# SurfaceEEG_V1_4.net
KiCad netlist of a schematic drawn in EAGLE
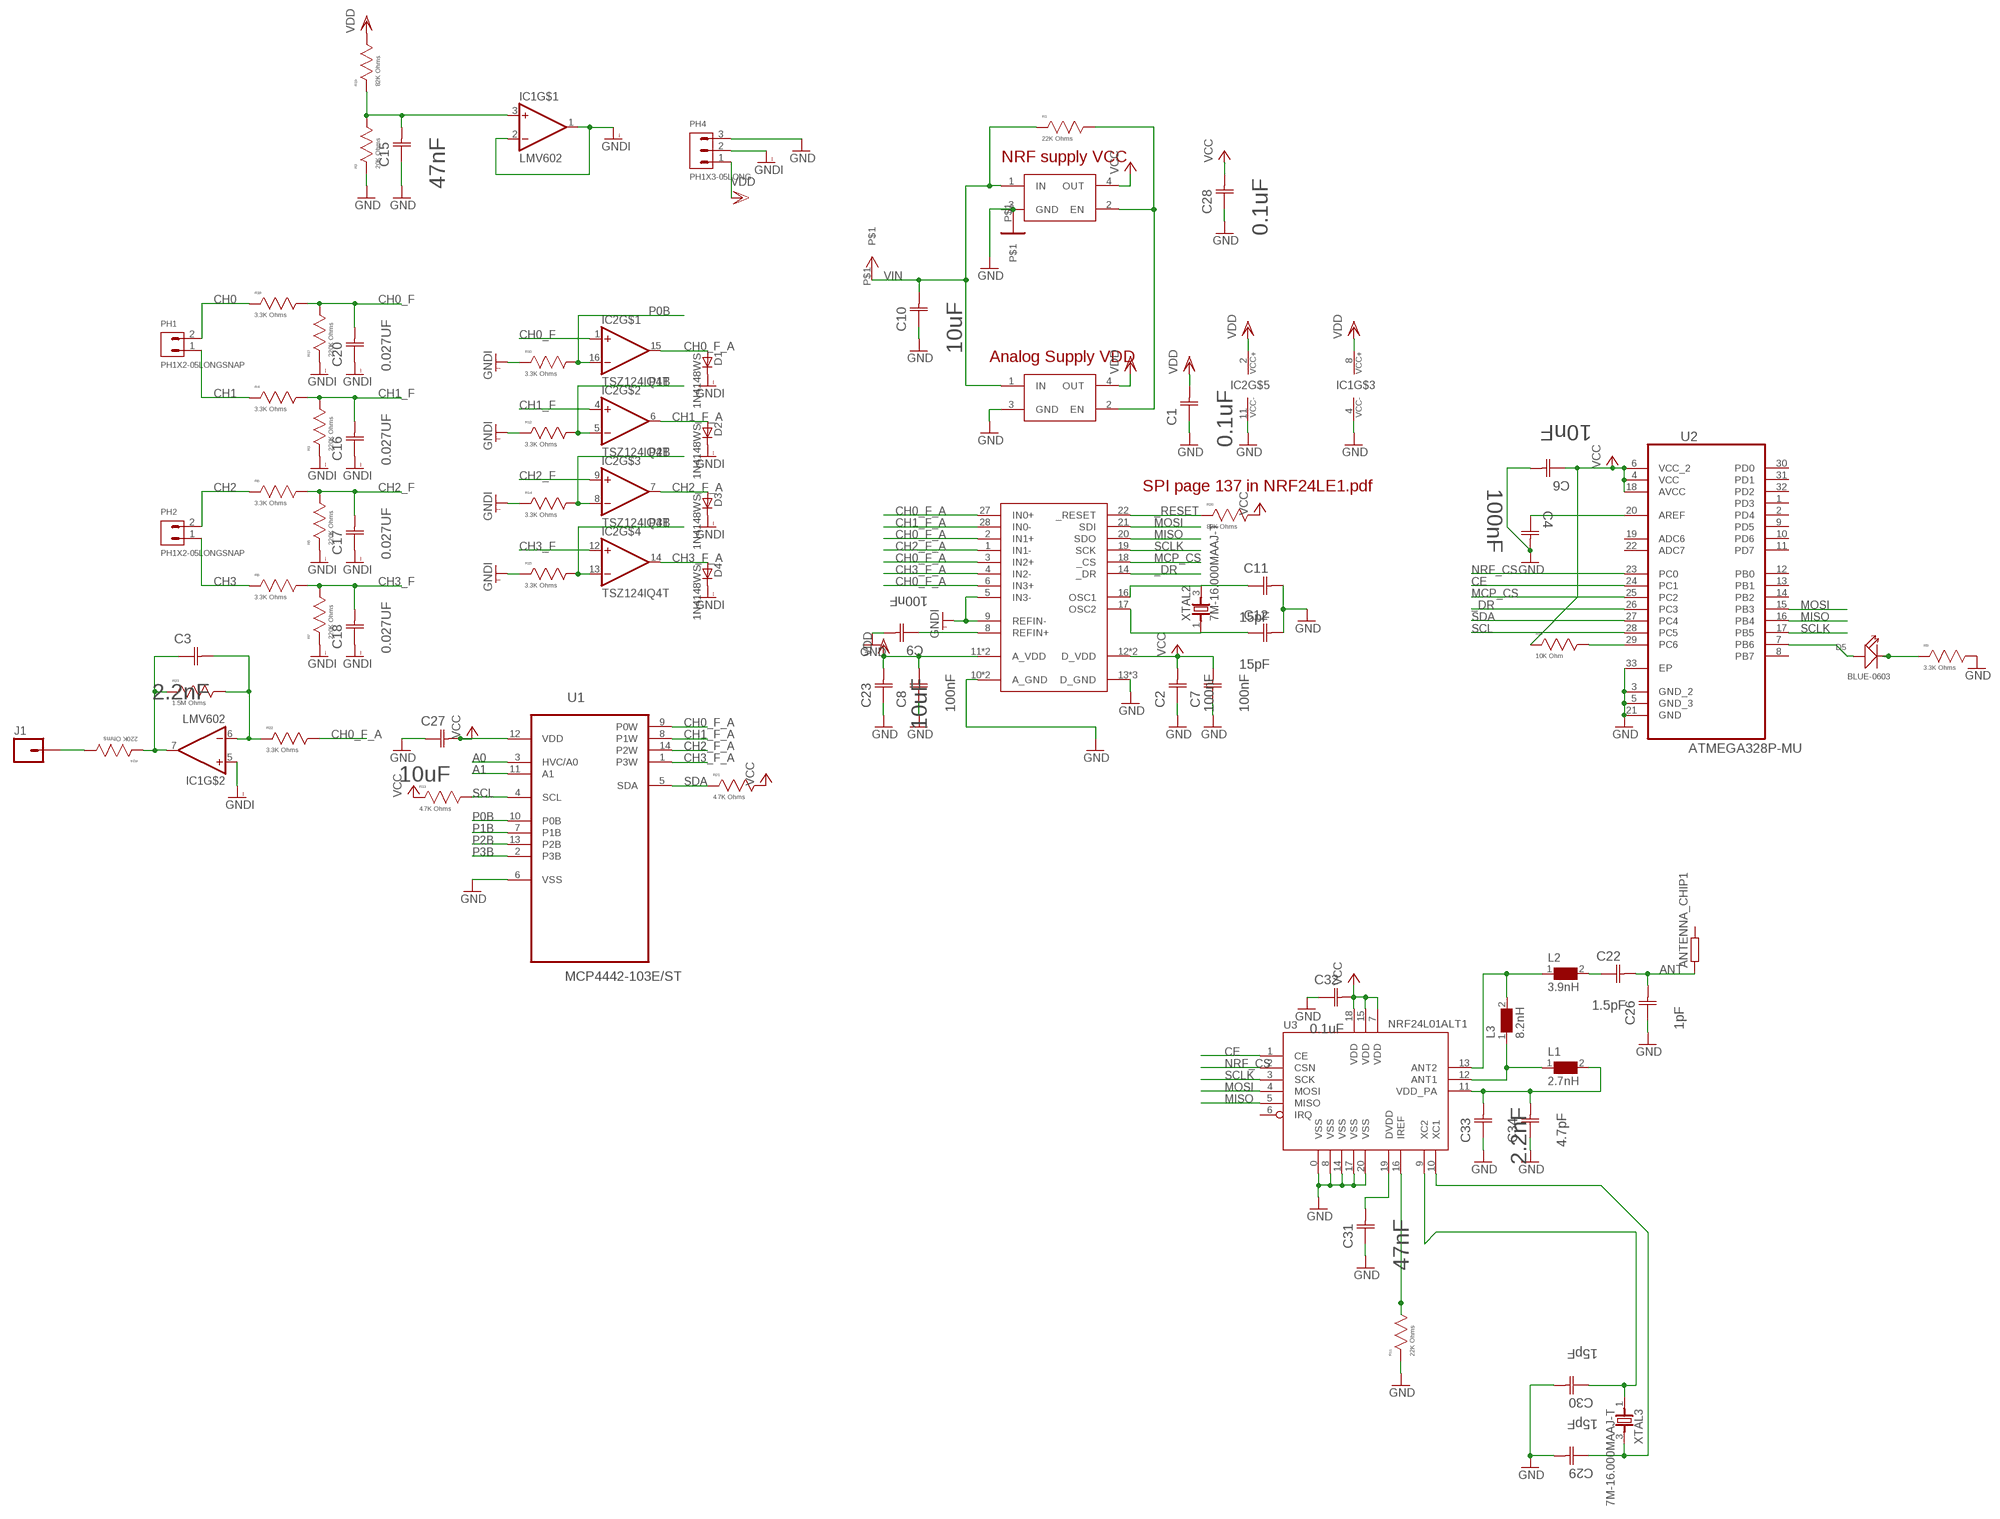
[diagram p0: schematic, sheet 1]

(export (version "E")
  (design (tool "Eeschema 10.0.6"))
  (components
    (comp (ref "ANTENNA_CHIP1")
      (value "R0805")
      (footprint "eagle-import:R0805")
      (libsource (lib "eagle-import") (part "R0805"))
    )
    (comp (ref "C1")
      (value "0.1uF")
      (footprint "eagle-import:CAPC1608X85N")
      (fields (field (name "MPN") "C0603C104K5RAC-TU") (field (name "TOLERANCE") "±10%"))
      (libsource (lib "eagle-import") (part "C0603C104K5RAC-TU"))
    )
    (comp (ref "C2")
      (value "100nF")
      (footprint "eagle-import:CAPC1608X90N")
      (fields (field (name "MPN") "06033C104JAT2A") (field (name "TOLERANCE") "±5%"))
      (libsource (lib "eagle-import") (part "06033C104JAT2A"))
    )
    (comp (ref "C3")
      (value "2.2nF")
      (footprint "eagle-import:CAPC1005X60N")
      (fields (field (name "MPN") "C0402C222K5RACTU") (field (name "TOLERANCE") "±10%"))
      (libsource (lib "eagle-import") (part "C0402C222K5RACTU"))
    )
    (comp (ref "C4")
      (value "100nF")
      (footprint "eagle-import:CAPC1608X85N")
      (fields (field (name "MPN") "C0603C104K4RACTU") (field (name "TOLERANCE") "±10%"))
      (libsource (lib "eagle-import") (part "C0603C104K4RACTU"))
    )
    (comp (ref "C6")
      (value "10nF")
      (footprint "eagle-import:CAPC1608X85N")
      (fields (field (name "MPN") "C0603C103J3GACTU") (field (name "TOLERANCE") "±5%"))
      (libsource (lib "eagle-import") (part "C0603C103J3GACTU"))
    )
    (comp (ref "C7")
      (value "100nF")
      (footprint "eagle-import:CAPC1608X90N")
      (fields (field (name "MPN") "06033C104JAT2A") (field (name "TOLERANCE") "±5%"))
      (libsource (lib "eagle-import") (part "06033C104JAT2A"))
    )
    (comp (ref "C8")
      (value "100nF")
      (footprint "eagle-import:CAPC1608X90N")
      (fields (field (name "MPN") "06033C104JAT2A") (field (name "TOLERANCE") "±5%"))
      (libsource (lib "eagle-import") (part "06033C104JAT2A"))
    )
    (comp (ref "C9")
      (value "100nF")
      (footprint "eagle-import:CAPC1608X90N")
      (fields (field (name "MPN") "06033C104JAT2A") (field (name "TOLERANCE") "±5%"))
      (libsource (lib "eagle-import") (part "06033C104JAT2A"))
    )
    (comp (ref "C10")
      (value "10uF")
      (footprint "eagle-import:CAPC1608X85N")
      (fields (field (name "MPN") "C0603C106M9PACTU") (field (name "TOLERANCE") "±20%"))
      (libsource (lib "eagle-import") (part "C0603C106M9PACTU"))
    )
    (comp (ref "C11")
      (value "15pF")
      (footprint "eagle-import:CAPC1005X60N")
      (fields (field (name "MPN") "UQCL2A150JAT2A/500") (field (name "TOLERANCE") "±5%"))
      (libsource (lib "eagle-import") (part "UQCL2A150JAT2A/500"))
    )
    (comp (ref "C12")
      (value "15pF")
      (footprint "eagle-import:CAPC1005X60N")
      (fields (field (name "MPN") "UQCL2A150JAT2A/500") (field (name "TOLERANCE") "±5%"))
      (libsource (lib "eagle-import") (part "UQCL2A150JAT2A/500"))
    )
    (comp (ref "C15")
      (value "47nF")
      (footprint "eagle-import:CAPC1608X85N")
      (fields (field (name "MPN") "C0603C473K1RACTU") (field (name "TOLERANCE") "±10%"))
      (libsource (lib "eagle-import") (part "C0603C473K1RACTU"))
    )
    (comp (ref "C16")
      (value "0.027UF")
      (footprint "eagle-import:CAPC1608X90N")
      (fields (field (name "MPN") "0603YC273JAT2A") (field (name "TOLERANCE") "±5%"))
      (libsource (lib "eagle-import") (part "0603YC273JAT2A"))
    )
    (comp (ref "C17")
      (value "0.027UF")
      (footprint "eagle-import:CAPC1608X90N")
      (fields (field (name "MPN") "0603YC273JAT2A") (field (name "TOLERANCE") "±5%"))
      (libsource (lib "eagle-import") (part "0603YC273JAT2A"))
    )
    (comp (ref "C18")
      (value "0.027UF")
      (footprint "eagle-import:CAPC1608X90N")
      (fields (field (name "MPN") "0603YC273JAT2A") (field (name "TOLERANCE") "±5%"))
      (libsource (lib "eagle-import") (part "0603YC273JAT2A"))
    )
    (comp (ref "C20")
      (value "0.027UF")
      (footprint "eagle-import:CAPC1608X90N")
      (fields (field (name "MPN") "0603YC273JAT2A") (field (name "TOLERANCE") "±5%"))
      (libsource (lib "eagle-import") (part "0603YC273JAT2A"))
    )
    (comp (ref "C22")
      (value "1.5pF")
      (footprint "eagle-import:CAPC1005X60N")
      (fields (field (name "MPN") "UQCL2A1R5BAT2A/500") (field (name "TOLERANCE") "±.1 pF"))
      (libsource (lib "eagle-import") (part "UQCL2A1R5BAT2A/500"))
    )
    (comp (ref "C23")
      (value "10uF")
      (footprint "eagle-import:CAPC1608X85N")
      (fields (field (name "MPN") "C0603C106M9PACTU") (field (name "TOLERANCE") "±20%"))
      (libsource (lib "eagle-import") (part "C0603C106M9PACTU"))
    )
    (comp (ref "C26")
      (value "1pF")
      (footprint "eagle-import:CAPC1005X60N")
      (fields (field (name "MPN") "UQCL2A1R0BAT2A/500") (field (name "TOLERANCE") "±.1 pF"))
      (libsource (lib "eagle-import") (part "UQCL2A1R0BAT2A/500"))
    )
    (comp (ref "C27")
      (value "10uF")
      (footprint "eagle-import:CAPC1608X85N")
      (fields (field (name "MPN") "C0603C106M9PACTU") (field (name "TOLERANCE") "±20%"))
      (libsource (lib "eagle-import") (part "C0603C106M9PACTU"))
    )
    (comp (ref "C28")
      (value "0.1uF")
      (footprint "eagle-import:CAPC1608X85N")
      (fields (field (name "MPN") "C0603C104K5RAC-TU") (field (name "TOLERANCE") "±10%"))
      (libsource (lib "eagle-import") (part "C0603C104K5RAC-TU"))
    )
    (comp (ref "C29")
      (value "15pF")
      (footprint "eagle-import:CAPC1005X60N")
      (fields (field (name "MPN") "UQCL2A150JAT2A/500") (field (name "TOLERANCE") "±5%"))
      (libsource (lib "eagle-import") (part "UQCL2A150JAT2A/500"))
    )
    (comp (ref "C30")
      (value "15pF")
      (footprint "eagle-import:CAPC1005X60N")
      (fields (field (name "MPN") "UQCL2A150JAT2A/500") (field (name "TOLERANCE") "±5%"))
      (libsource (lib "eagle-import") (part "UQCL2A150JAT2A/500"))
    )
    (comp (ref "C31")
      (value "47nF")
      (footprint "eagle-import:CAPC1608X85N")
      (fields (field (name "MPN") "C0603C473K1RACTU") (field (name "TOLERANCE") "±10%"))
      (libsource (lib "eagle-import") (part "C0603C473K1RACTU"))
    )
    (comp (ref "C32")
      (value "0.1uF")
      (footprint "eagle-import:CAPC1005X60N")
      (fields (field (name "MPN") "04023C104KAT2A") (field (name "TOLERANCE") "±10%"))
      (libsource (lib "eagle-import") (part "04023C104KAT2A"))
    )
    (comp (ref "C33")
      (value "2.2nF")
      (footprint "eagle-import:CAPC1005X60N")
      (fields (field (name "MPN") "C0402C222K5RACTU") (field (name "TOLERANCE") "±10%"))
      (libsource (lib "eagle-import") (part "C0402C222K5RACTU"))
    )
    (comp (ref "C34")
      (value "4.7pF")
      (footprint "eagle-import:CAPC1005X60N")
      (fields (field (name "MPN") "UQCL2A4R7CAT2A/500") (field (name "TOLERANCE") "±.25 pF"))
      (libsource (lib "eagle-import") (part "UQCL2A4R7CAT2A/500"))
    )
    (comp (ref "D1")
      (value "1N4148WS")
      (footprint "eagle-import:SOD323F")
      (fields (field (name "MPN") "1N4148WS-7-F"))
      (libsource (lib "eagle-import") (part "1N4148WS"))
    )
    (comp (ref "D2")
      (value "1N4148WS")
      (footprint "eagle-import:SOD323F")
      (fields (field (name "MPN") "1N4148WS-7-F"))
      (libsource (lib "eagle-import") (part "1N4148WS"))
    )
    (comp (ref "D3")
      (value "1N4148WS")
      (footprint "eagle-import:SOD323F")
      (fields (field (name "MPN") "1N4148WS-7-F"))
      (libsource (lib "eagle-import") (part "1N4148WS"))
    )
    (comp (ref "D4")
      (value "1N4148WS")
      (footprint "eagle-import:SOD323F")
      (fields (field (name "MPN") "1N4148WS-7-F"))
      (libsource (lib "eagle-import") (part "1N4148WS"))
    )
    (comp (ref "D5")
      (value "BLUE-0603")
      (footprint "eagle-import:LED-0603")
      (fields (field (name "MPN") "19-217-BHC-ZL1M2RY-3T"))
      (libsource (lib "eagle-import") (part "SMD-LED-CLEAR-BLUE(0603)"))
    )
    (comp (ref "IC1")
      (value "LMV602")
      (footprint "eagle-import:VSSOP8")
      (fields (field (name "MPN") "LMV602MM/NOPB"))
      (libsource (lib "eagle-import") (part "LMV602"))
    )
    (comp (ref "IC2")
      (value "TSZ124IQ4T")
      (footprint "eagle-import:QFN16")
      (libsource (lib "eagle-import") (part "TSZ124IQ4T"))
    )
    (comp (ref "J1")
      (value "M01SMD-4.5X1.5")
      (footprint "eagle-import:PAD-1.5X4.5")
      (libsource (lib "eagle-import") (part "M01SMD-4.5X1.5"))
    )
    (comp (ref "L1")
      (value "2.7nH")
      (footprint "eagle-import:WE-KI_0402A")
      (fields (field (name "MPN") "744765027A"))
      (libsource (lib "eagle-import") (part "WE-KI_0402A-744765027A"))
    )
    (comp (ref "L2")
      (value "3.9nH")
      (footprint "eagle-import:WE-KI_0402A")
      (fields (field (name "MPN") "744765039A"))
      (libsource (lib "eagle-import") (part "WE-KI_0402A-744765039A"))
    )
    (comp (ref "L3")
      (value "8.2nH")
      (footprint "eagle-import:WE-KI_0402A")
      (fields (field (name "MPN") "744765082A"))
      (libsource (lib "eagle-import") (part "WE-KI_0402A-744765082A"))
    )
    (comp (ref "PH1")
      (value "PH1X2-05LONGSNAP")
      (footprint "eagle-import:PHLS005-1-2")
      (libsource (lib "eagle-import") (part "PH1X2-05LONGSNAP"))
    )
    (comp (ref "PH2")
      (value "PH1X2-05LONGSNAP")
      (footprint "eagle-import:PHLS005-1-2")
      (libsource (lib "eagle-import") (part "PH1X2-05LONGSNAP"))
    )
    (comp (ref "PH4")
      (value "PH1X3-05LONG")
      (footprint "eagle-import:PHL005-1-3")
      (libsource (lib "eagle-import") (part "PH1X3-05LONG"))
    )
    (comp (ref "R1")
      (value "22K Ohms")
      (footprint "eagle-import:RESC1608X60N")
      (fields (field (name "MPN") "RC0603FR-0722KL") (field (name "TOLERANCE") "±1%"))
      (libsource (lib "eagle-import") (part "RC0603FR-0722KL"))
    )
    (comp (ref "R2")
      (value "20K Ohms")
      (footprint "eagle-import:RESC1608X60N")
      (fields (field (name "MPN") "RC0603FR-0720KL") (field (name "TOLERANCE") "±1%"))
      (libsource (lib "eagle-import") (part "RC0603FR-0720KL"))
    )
    (comp (ref "R3")
      (value "220K Ohms")
      (footprint "eagle-import:RESC1608X60N")
      (fields (field (name "MPN") "RC0603FR-07220KL") (field (name "TOLERANCE") "±1%"))
      (libsource (lib "eagle-import") (part "RC0603FR-07220KL"))
    )
    (comp (ref "R4")
      (value "3.3K Ohms")
      (footprint "eagle-import:RESC1608X60N")
      (fields (field (name "MPN") "RC0603FR-073K3L") (field (name "TOLERANCE") "±1%"))
      (libsource (lib "eagle-import") (part "RC0603FR-073K3L"))
    )
    (comp (ref "R5")
      (value "220K Ohms")
      (footprint "eagle-import:RESC1608X60N")
      (fields (field (name "MPN") "RC0603FR-07220KL") (field (name "TOLERANCE") "±1%"))
      (libsource (lib "eagle-import") (part "RC0603FR-07220KL"))
    )
    (comp (ref "R6")
      (value "3.3K Ohms")
      (footprint "eagle-import:RESC1608X60N")
      (fields (field (name "MPN") "RC0603FR-073K3L") (field (name "TOLERANCE") "±1%"))
      (libsource (lib "eagle-import") (part "RC0603FR-073K3L"))
    )
    (comp (ref "R7")
      (value "220K Ohms")
      (footprint "eagle-import:RESC1608X60N")
      (fields (field (name "MPN") "RC0603FR-07220KL") (field (name "TOLERANCE") "±1%"))
      (libsource (lib "eagle-import") (part "RC0603FR-07220KL"))
    )
    (comp (ref "R8")
      (value "3.3K Ohms")
      (footprint "eagle-import:RESC1608X60N")
      (fields (field (name "MPN") "RC0603FR-073K3L") (field (name "TOLERANCE") "±1%"))
      (libsource (lib "eagle-import") (part "RC0603FR-073K3L"))
    )
    (comp (ref "R9")
      (value "3.3K Ohms")
      (footprint "eagle-import:RESC1608X60N")
      (fields (field (name "MPN") "RC0603FR-073K3L") (field (name "TOLERANCE") "±1%"))
      (libsource (lib "eagle-import") (part "RC0603FR-073K3L"))
    )
    (comp (ref "R10")
      (value "3.3K Ohms")
      (footprint "eagle-import:RESC1608X60N")
      (fields (field (name "MPN") "RC0603FR-073K3L") (field (name "TOLERANCE") "±1%"))
      (libsource (lib "eagle-import") (part "RC0603FR-073K3L"))
    )
    (comp (ref "R11")
      (value "22K Ohms")
      (footprint "eagle-import:RESC1608X60N")
      (fields (field (name "MPN") "RC0603FR-0722KL") (field (name "TOLERANCE") "±1%"))
      (libsource (lib "eagle-import") (part "RC0603FR-0722KL"))
    )
    (comp (ref "R12")
      (value "3.3K Ohms")
      (footprint "eagle-import:RESC1608X60N")
      (fields (field (name "MPN") "RC0603FR-073K3L") (field (name "TOLERANCE") "±1%"))
      (libsource (lib "eagle-import") (part "RC0603FR-073K3L"))
    )
    (comp (ref "R13")
      (value "4.7K Ohms")
      (footprint "eagle-import:RESC1005X40N")
      (fields (field (name "MPN") "9C04021A4701JLHF3") (field (name "TOLERANCE") "±5%"))
      (libsource (lib "eagle-import") (part "9C04021A4701JLHF3"))
    )
    (comp (ref "R14")
      (value "3.3K Ohms")
      (footprint "eagle-import:RESC1608X60N")
      (fields (field (name "MPN") "RC0603FR-073K3L") (field (name "TOLERANCE") "±1%"))
      (libsource (lib "eagle-import") (part "RC0603FR-073K3L"))
    )
    (comp (ref "R15")
      (value "3.3K Ohms")
      (footprint "eagle-import:RESC1608X60N")
      (fields (field (name "MPN") "RC0603FR-073K3L") (field (name "TOLERANCE") "±1%"))
      (libsource (lib "eagle-import") (part "RC0603FR-073K3L"))
    )
    (comp (ref "R16")
      (value "10K Ohm")
      (footprint "eagle-import:RESC1608X60N")
      (fields (field (name "MPN") "9C06031A1002JLHFT") (field (name "TOLERANCE") "±5%"))
      (libsource (lib "eagle-import") (part "9C06031A1002JLHFT"))
    )
    (comp (ref "R17")
      (value "220K Ohms")
      (footprint "eagle-import:RESC1608X60N")
      (fields (field (name "MPN") "RC0603FR-07220KL") (field (name "TOLERANCE") "±1%"))
      (libsource (lib "eagle-import") (part "RC0603FR-07220KL"))
    )
    (comp (ref "R18")
      (value "3.3K Ohms")
      (footprint "eagle-import:RESC1608X60N")
      (fields (field (name "MPN") "RC0603FR-073K3L") (field (name "TOLERANCE") "±1%"))
      (libsource (lib "eagle-import") (part "RC0603FR-073K3L"))
    )
    (comp (ref "R19")
      (value "82K Ohms")
      (footprint "eagle-import:RESC1608X60N")
      (fields (field (name "MPN") "RT0603FRE0782KL") (field (name "TOLERANCE") "±1%"))
      (libsource (lib "eagle-import") (part "RT0603FRE0782KL"))
    )
    (comp (ref "R20")
      (value "82K Ohms")
      (footprint "eagle-import:RESC1608X60N")
      (fields (field (name "MPN") "RT0603FRE0782KL") (field (name "TOLERANCE") "±1%"))
      (libsource (lib "eagle-import") (part "RT0603FRE0782KL"))
    )
    (comp (ref "R21")
      (value "4.7K Ohms")
      (footprint "eagle-import:RESC1005X40N")
      (fields (field (name "MPN") "9C04021A4701JLHF3") (field (name "TOLERANCE") "±5%"))
      (libsource (lib "eagle-import") (part "9C04021A4701JLHF3"))
    )
    (comp (ref "R22")
      (value "3.3K Ohms")
      (footprint "eagle-import:RESC1608X60N")
      (fields (field (name "MPN") "RC0603FR-073K3L") (field (name "TOLERANCE") "±1%"))
      (libsource (lib "eagle-import") (part "RC0603FR-073K3L"))
    )
    (comp (ref "R23")
      (value "1.5M Ohms")
      (footprint "eagle-import:RESC1608X60N")
      (fields (field (name "MPN") "RC0603FR-071M5L") (field (name "TOLERANCE") "±1%"))
      (libsource (lib "eagle-import") (part "RC0603FR-071M5L"))
    )
    (comp (ref "R24")
      (value "220K Ohms")
      (footprint "eagle-import:RESC1608X60N")
      (fields (field (name "MPN") "RC0603FR-07220KL") (field (name "TOLERANCE") "±1%"))
      (libsource (lib "eagle-import") (part "RC0603FR-07220KL"))
    )
    (comp (ref "U$1")
      (value "NCP103")
      (footprint "eagle-import:UDFN4-1_1")
      (fields (field (name "MPN") "NCP103AMX330TCG"))
      (libsource (lib "eagle-import") (part "NCP103"))
    )
    (comp (ref "U$2")
      (value "NCP103")
      (footprint "eagle-import:UDFN4-1_1")
      (fields (field (name "MPN") "NCP103AMX330TCG"))
      (libsource (lib "eagle-import") (part "NCP103"))
    )
    (comp (ref "U$3")
      (value "MCP3912")
      (footprint "eagle-import:QFN28")
      (fields (field (name "MPN") "MCP3912A1-E/MQ "))
      (libsource (lib "eagle-import") (part "MCP3912"))
    )
    (comp (ref "U$4")
      (value "VCC")
      (footprint "eagle-import:VCC-PAD")
      (libsource (lib "eagle-import") (part "VCC"))
    )
    (comp (ref "U$5")
      (value "GND")
      (footprint "eagle-import:GND-PAD")
      (libsource (lib "eagle-import") (part "GND"))
    )
    (comp (ref "U1")
      (value "MCP4442-103E/ST")
      (footprint "eagle-import:SOP65P640X120-14N")
      (libsource (lib "eagle-import") (part "MCP4442-103E/ST"))
    )
    (comp (ref "U2")
      (value "ATMEGA328P-MU")
      (footprint "eagle-import:QFN50P500X500X100-33N")
      (libsource (lib "eagle-import") (part "ATMEGA328P-MU"))
    )
    (comp (ref "U3")
      (value "NRF24L01ALT1")
      (footprint "eagle-import:QFN20_ALT1")
      (libsource (lib "eagle-import") (part "NRF24L01ALT1"))
    )
    (comp (ref "XTAL2")
      (value "7M-16.000MAAJ-T")
      (footprint "eagle-import:TXC_7M-16.000MAAJ-T")
      (fields (field (name "MPN") "7M-16.000MAAJ-T "))
      (libsource (lib "eagle-import") (part "7M-16.000MAAJ-T"))
    )
    (comp (ref "XTAL3")
      (value "7M-16.000MAAJ-T")
      (footprint "eagle-import:TXC_7M-16.000MAAJ-T")
      (fields (field (name "MPN") "7M-16.000MAAJ-T "))
      (libsource (lib "eagle-import") (part "7M-16.000MAAJ-T"))
    )
  )
  (nets
    (net (code "1") (name "/A0") (class "Default")
      (node (ref "U1") (pin "3") (pinfunction "HVC/A0_3") (pintype "input"))
    )
    (net (code "2") (name "/A1") (class "Default")
      (node (ref "U1") (pin "11") (pinfunction "A1_11") (pintype "input"))
    )
    (net (code "3") (name "/ANT") (class "Default")
      (node (ref "ANTENNA_CHIP1") (pin "1") (pinfunction "1_1") (pintype "passive"))
      (node (ref "C22") (pin "1") (pinfunction "C2_1") (pintype "passive"))
      (node (ref "C26") (pin "1") (pinfunction "C2_1") (pintype "passive"))
    )
    (net (code "4") (name "/CE") (class "Default")
      (node (ref "U2") (pin "24") (pinfunction "PC1_24") (pintype "bidirectional"))
      (node (ref "U3") (pin "1") (pinfunction "CE_1") (pintype "input"))
    )
    (net (code "5") (name "/CH0") (class "Default")
      (node (ref "PH1") (pin "2") (pinfunction "2_2") (pintype "bidirectional"))
      (node (ref "R18") (pin "2") (pinfunction "R2_2") (pintype "passive"))
    )
    (net (code "6") (name "/CH0_F") (class "Default")
      (node (ref "C20") (pin "2") (pinfunction "C2_2") (pintype "passive"))
      (node (ref "IC2") (pin "1") (pinfunction "IN+_1") (pintype "input"))
      (node (ref "R17") (pin "1") (pinfunction "R1_1") (pintype "passive"))
      (node (ref "R18") (pin "1") (pinfunction "R1_1") (pintype "passive"))
    )
    (net (code "7") (name "/CH0_F_A") (class "Default")
      (node (ref "D1") (pin "A") (pinfunction "A_A") (pintype "passive"))
      (node (ref "IC2") (pin "15") (pinfunction "OUT_15") (pintype "output"))
      (node (ref "R22") (pin "1") (pinfunction "R1_1") (pintype "passive"))
      (node (ref "U$3") (pin "2") (pinfunction "IN1+_2") (pintype "bidirectional"))
      (node (ref "U$3") (pin "27") (pinfunction "IN0+_27") (pintype "bidirectional"))
      (node (ref "U$3") (pin "3") (pinfunction "IN2+_3") (pintype "bidirectional"))
      (node (ref "U$3") (pin "6") (pinfunction "IN3+_6") (pintype "bidirectional"))
      (node (ref "U1") (pin "9") (pinfunction "P0W_9") (pintype "passive"))
    )
    (net (code "8") (name "/CH1") (class "Default")
      (node (ref "PH1") (pin "1") (pinfunction "1_1") (pintype "bidirectional"))
      (node (ref "R4") (pin "2") (pinfunction "R2_2") (pintype "passive"))
    )
    (net (code "9") (name "/CH1_F") (class "Default")
      (node (ref "C16") (pin "2") (pinfunction "C2_2") (pintype "passive"))
      (node (ref "IC2") (pin "4") (pinfunction "IN+_4") (pintype "input"))
      (node (ref "R3") (pin "1") (pinfunction "R1_1") (pintype "passive"))
      (node (ref "R4") (pin "1") (pinfunction "R1_1") (pintype "passive"))
    )
    (net (code "10") (name "/CH1_F_A") (class "Default")
      (node (ref "D2") (pin "A") (pinfunction "A_A") (pintype "passive"))
      (node (ref "IC2") (pin "6") (pinfunction "OUT_6") (pintype "output"))
      (node (ref "U$3") (pin "28") (pinfunction "IN0-_28") (pintype "bidirectional"))
      (node (ref "U1") (pin "8") (pinfunction "P1W_8") (pintype "passive"))
    )
    (net (code "11") (name "/CH2") (class "Default")
      (node (ref "PH2") (pin "2") (pinfunction "2_2") (pintype "bidirectional"))
      (node (ref "R6") (pin "2") (pinfunction "R2_2") (pintype "passive"))
    )
    (net (code "12") (name "/CH2_F") (class "Default")
      (node (ref "C17") (pin "2") (pinfunction "C2_2") (pintype "passive"))
      (node (ref "IC2") (pin "9") (pinfunction "IN+_9") (pintype "input"))
      (node (ref "R5") (pin "1") (pinfunction "R1_1") (pintype "passive"))
      (node (ref "R6") (pin "1") (pinfunction "R1_1") (pintype "passive"))
    )
    (net (code "13") (name "/CH2_F_A") (class "Default")
      (node (ref "D3") (pin "A") (pinfunction "A_A") (pintype "passive"))
      (node (ref "IC2") (pin "7") (pinfunction "OUT_7") (pintype "output"))
      (node (ref "U$3") (pin "1") (pinfunction "IN1-_1") (pintype "bidirectional"))
      (node (ref "U1") (pin "14") (pinfunction "P2W_14") (pintype "passive"))
    )
    (net (code "14") (name "/CH3") (class "Default")
      (node (ref "PH2") (pin "1") (pinfunction "1_1") (pintype "bidirectional"))
      (node (ref "R8") (pin "2") (pinfunction "R2_2") (pintype "passive"))
    )
    (net (code "15") (name "/CH3_F") (class "Default")
      (node (ref "C18") (pin "2") (pinfunction "C2_2") (pintype "passive"))
      (node (ref "IC2") (pin "12") (pinfunction "IN+_12") (pintype "input"))
      (node (ref "R7") (pin "1") (pinfunction "R1_1") (pintype "passive"))
      (node (ref "R8") (pin "1") (pinfunction "R1_1") (pintype "passive"))
    )
    (net (code "16") (name "/CH3_F_A") (class "Default")
      (node (ref "D4") (pin "A") (pinfunction "A_A") (pintype "passive"))
      (node (ref "IC2") (pin "14") (pinfunction "OUT_14") (pintype "output"))
      (node (ref "U$3") (pin "4") (pinfunction "IN2-_4") (pintype "bidirectional"))
      (node (ref "U1") (pin "1") (pinfunction "P3W_1") (pintype "passive"))
    )
    (net (code "17") (name "/MCP_CS") (class "Default")
      (node (ref "U$3") (pin "18") (pinfunction "_CS_18") (pintype "bidirectional"))
      (node (ref "U2") (pin "25") (pinfunction "PC2_25") (pintype "bidirectional"))
    )
    (net (code "18") (name "/MISO") (class "Default")
      (node (ref "U$3") (pin "20") (pinfunction "SDO_20") (pintype "bidirectional"))
      (node (ref "U2") (pin "16") (pinfunction "PB4_16") (pintype "bidirectional"))
      (node (ref "U3") (pin "5") (pinfunction "MISO_5") (pintype "output"))
    )
    (net (code "19") (name "/MOSI") (class "Default")
      (node (ref "U$3") (pin "21") (pinfunction "SDI_21") (pintype "bidirectional"))
      (node (ref "U2") (pin "15") (pinfunction "PB3_15") (pintype "bidirectional"))
      (node (ref "U3") (pin "4") (pinfunction "MOSI_4") (pintype "input"))
    )
    (net (code "20") (name "/NRF_CS") (class "Default")
      (node (ref "U2") (pin "23") (pinfunction "PC0_23") (pintype "bidirectional"))
      (node (ref "U3") (pin "2") (pinfunction "CSN_2") (pintype "input"))
    )
    (net (code "21") (name "/P0B") (class "Default")
      (node (ref "IC2") (pin "16") (pinfunction "IN-_16") (pintype "input"))
      (node (ref "R10") (pin "1") (pinfunction "R1_1") (pintype "passive"))
      (node (ref "U1") (pin "10") (pinfunction "P0B_10") (pintype "passive"))
    )
    (net (code "22") (name "/P1B") (class "Default")
      (node (ref "IC2") (pin "5") (pinfunction "IN-_5") (pintype "input"))
      (node (ref "R12") (pin "1") (pinfunction "R1_1") (pintype "passive"))
      (node (ref "U1") (pin "7") (pinfunction "P1B_7") (pintype "passive"))
    )
    (net (code "23") (name "/P2B") (class "Default")
      (node (ref "IC2") (pin "8") (pinfunction "IN-_8") (pintype "input"))
      (node (ref "R14") (pin "1") (pinfunction "R1_1") (pintype "passive"))
      (node (ref "U1") (pin "13") (pinfunction "P2B_13") (pintype "passive"))
    )
    (net (code "24") (name "/P3B") (class "Default")
      (node (ref "IC2") (pin "13") (pinfunction "IN-_13") (pintype "input"))
      (node (ref "R15") (pin "1") (pinfunction "R1_1") (pintype "passive"))
      (node (ref "U1") (pin "2") (pinfunction "P3B_2") (pintype "passive"))
    )
    (net (code "25") (name "/SCL") (class "Default")
      (node (ref "R13") (pin "1") (pinfunction "R1_1") (pintype "passive"))
      (node (ref "U1") (pin "4") (pinfunction "SCL_4") (pintype "input"))
      (node (ref "U2") (pin "28") (pinfunction "PC5_28") (pintype "bidirectional"))
    )
    (net (code "26") (name "/SCLK") (class "Default")
      (node (ref "U$3") (pin "19") (pinfunction "SCK_19") (pintype "bidirectional"))
      (node (ref "U2") (pin "17") (pinfunction "PB5_17") (pintype "bidirectional"))
      (node (ref "U3") (pin "3") (pinfunction "SCK_3") (pintype "input"))
    )
    (net (code "27") (name "/SDA") (class "Default")
      (node (ref "R21") (pin "2") (pinfunction "R2_2") (pintype "passive"))
      (node (ref "U1") (pin "5") (pinfunction "SDA_5") (pintype "bidirectional"))
      (node (ref "U2") (pin "27") (pinfunction "PC4_27") (pintype "bidirectional"))
    )
    (net (code "28") (name "/VIN") (class "Default")
      (node (ref "C10") (pin "2") (pinfunction "C2_2") (pintype "passive"))
      (node (ref "R1") (pin "2") (pinfunction "R2_2") (pintype "passive"))
      (node (ref "U$1") (pin "1") (pinfunction "IN_1") (pintype "bidirectional"))
      (node (ref "U$2") (pin "1") (pinfunction "IN_1") (pintype "bidirectional"))
      (node (ref "U$4") (pin "P$1") (pinfunction "P$1_P$1") (pintype "bidirectional"))
    )
    (net (code "29") (name "/_DR") (class "Default")
      (node (ref "U$3") (pin "14") (pinfunction "_DR_14") (pintype "bidirectional"))
      (node (ref "U2") (pin "26") (pinfunction "PC3_26") (pintype "bidirectional"))
    )
    (net (code "30") (name "/_RESET") (class "Default")
      (node (ref "R20") (pin "2") (pinfunction "R2_2") (pintype "passive"))
      (node (ref "U$3") (pin "22") (pinfunction "_RESET_22") (pintype "bidirectional"))
    )
    (net (code "31") (name "GND") (class "Default")
      (node (ref "C1") (pin "1") (pinfunction "C1_1") (pintype "passive"))
      (node (ref "C10") (pin "1") (pinfunction "C1_1") (pintype "passive"))
      (node (ref "C11") (pin "1") (pinfunction "C2_1") (pintype "passive"))
      (node (ref "C12") (pin "1") (pinfunction "C2_1") (pintype "passive"))
      (node (ref "C15") (pin "1") (pinfunction "C1_1") (pintype "passive"))
      (node (ref "C2") (pin "1") (pinfunction "C1_1") (pintype "passive"))
      (node (ref "C23") (pin "1") (pinfunction "C1_1") (pintype "passive"))
      (node (ref "C26") (pin "2") (pinfunction "C1_2") (pintype "passive"))
      (node (ref "C27") (pin "1") (pinfunction "C1_1") (pintype "passive"))
      (node (ref "C28") (pin "1") (pinfunction "C1_1") (pintype "passive"))
      (node (ref "C29") (pin "1") (pinfunction "C2_1") (pintype "passive"))
      (node (ref "C30") (pin "1") (pinfunction "C2_1") (pintype "passive"))
      (node (ref "C31") (pin "1") (pinfunction "C1_1") (pintype "passive"))
      (node (ref "C32") (pin "2") (pinfunction "C1_2") (pintype "passive"))
      (node (ref "C33") (pin "1") (pinfunction "C1_1") (pintype "passive"))
      (node (ref "C34") (pin "2") (pinfunction "C1_2") (pintype "passive"))
      (node (ref "C4") (pin "2") (pinfunction "C2_2") (pintype "passive"))
      (node (ref "C6") (pin "2") (pinfunction "C2_2") (pintype "passive"))
      (node (ref "C7") (pin "1") (pinfunction "C1_1") (pintype "passive"))
      (node (ref "C8") (pin "1") (pinfunction "C1_1") (pintype "passive"))
      (node (ref "C9") (pin "2") (pinfunction "C2_2") (pintype "passive"))
      (node (ref "IC1") (pin "4") (pinfunction "VCC-_4") (pintype "power_in"))
      (node (ref "IC2") (pin "11") (pinfunction "VCC-_11") (pintype "power_in"))
      (node (ref "PH4") (pin "3") (pinfunction "3_3") (pintype "bidirectional"))
      (node (ref "R11") (pin "2") (pinfunction "R2_2") (pintype "passive"))
      (node (ref "R2") (pin "2") (pinfunction "R2_2") (pintype "passive"))
      (node (ref "R9") (pin "1") (pinfunction "R1_1") (pintype "passive"))
      (node (ref "U$1") (pin "3") (pinfunction "GND_3") (pintype "bidirectional"))
      (node (ref "U$2") (pin "3") (pinfunction "GND_3") (pintype "bidirectional"))
      (node (ref "U$3") (pin "10") (pinfunction "A_GND_10") (pintype "bidirectional"))
      (node (ref "U$3") (pin "13") (pinfunction "D_GND_13") (pintype "bidirectional"))
      (node (ref "U$3") (pin "15") (pinfunction "D_GND_15") (pintype "bidirectional"))
      (node (ref "U$3") (pin "23") (pinfunction "D_GND_23") (pintype "bidirectional"))
      (node (ref "U$3") (pin "26") (pinfunction "A_GND_26") (pintype "bidirectional"))
      (node (ref "U$5") (pin "P$1") (pinfunction "P$1_P$1") (pintype "bidirectional"))
      (node (ref "U1") (pin "6") (pinfunction "VSS_6") (pintype "power_in"))
      (node (ref "U2") (pin "21") (pinfunction "GND_21") (pintype "passive"))
      (node (ref "U2") (pin "3") (pinfunction "GND_2_3") (pintype "passive"))
      (node (ref "U2") (pin "33") (pinfunction "EP_33") (pintype "passive"))
      (node (ref "U2") (pin "5") (pinfunction "GND_3_5") (pintype "passive"))
      (node (ref "U3") (pin "0") (pinfunction "VSS_0") (pintype "power_in"))
      (node (ref "U3") (pin "14") (pinfunction "VSS_14") (pintype "power_in"))
      (node (ref "U3") (pin "17") (pinfunction "VSS_17") (pintype "power_in"))
      (node (ref "U3") (pin "20") (pinfunction "VSS_20") (pintype "power_in"))
      (node (ref "U3") (pin "8") (pinfunction "VSS_8") (pintype "power_in"))
    )
    (net (code "32") (name "GNDI") (class "Default")
      (node (ref "C16") (pin "1") (pinfunction "C1_1") (pintype "passive"))
      (node (ref "C17") (pin "1") (pinfunction "C1_1") (pintype "passive"))
      (node (ref "C18") (pin "1") (pinfunction "C1_1") (pintype "passive"))
      (node (ref "C20") (pin "1") (pinfunction "C1_1") (pintype "passive"))
      (node (ref "D1") (pin "C") (pinfunction "C_C") (pintype "passive"))
      (node (ref "D2") (pin "C") (pinfunction "C_C") (pintype "passive"))
      (node (ref "D3") (pin "C") (pinfunction "C_C") (pintype "passive"))
      (node (ref "D4") (pin "C") (pinfunction "C_C") (pintype "passive"))
      (node (ref "IC1") (pin "1") (pinfunction "OUT_1") (pintype "output"))
      (node (ref "IC1") (pin "2") (pinfunction "IN-_2") (pintype "input"))
      (node (ref "IC1") (pin "5") (pinfunction "IN+_5") (pintype "input"))
      (node (ref "PH4") (pin "2") (pinfunction "2_2") (pintype "bidirectional"))
      (node (ref "R10") (pin "2") (pinfunction "R2_2") (pintype "passive"))
      (node (ref "R12") (pin "2") (pinfunction "R2_2") (pintype "passive"))
      (node (ref "R14") (pin "2") (pinfunction "R2_2") (pintype "passive"))
      (node (ref "R15") (pin "2") (pinfunction "R2_2") (pintype "passive"))
      (node (ref "R17") (pin "2") (pinfunction "R2_2") (pintype "passive"))
      (node (ref "R3") (pin "2") (pinfunction "R2_2") (pintype "passive"))
      (node (ref "R5") (pin "2") (pinfunction "R2_2") (pintype "passive"))
      (node (ref "R7") (pin "2") (pinfunction "R2_2") (pintype "passive"))
      (node (ref "U$3") (pin "5") (pinfunction "IN3-_5") (pintype "bidirectional"))
      (node (ref "U$3") (pin "9") (pinfunction "REFIN-_9") (pintype "bidirectional"))
    )
    (net (code "33") (name "Net-(C3-C1)") (class "Default")
      (node (ref "C3") (pin "1") (pinfunction "C1_1") (pintype "passive"))
      (node (ref "IC1") (pin "7") (pinfunction "OUT_7") (pintype "output"))
      (node (ref "R23") (pin "2") (pinfunction "R2_2") (pintype "passive"))
      (node (ref "R24") (pin "2") (pinfunction "R2_2") (pintype "passive"))
    )
    (net (code "34") (name "Net-(C3-C2)") (class "Default")
      (node (ref "C3") (pin "2") (pinfunction "C2_2") (pintype "passive"))
      (node (ref "IC1") (pin "6") (pinfunction "IN-_6") (pintype "input"))
      (node (ref "R22") (pin "2") (pinfunction "R2_2") (pintype "passive"))
      (node (ref "R23") (pin "1") (pinfunction "R1_1") (pintype "passive"))
    )
    (net (code "35") (name "Net-(C4-C1)") (class "Default")
      (node (ref "C4") (pin "1") (pinfunction "C1_1") (pintype "passive"))
      (node (ref "U2") (pin "20") (pinfunction "AREF_20") (pintype "input"))
    )
    (net (code "36") (name "Net-(C9-C1)") (class "Default")
      (node (ref "C9") (pin "1") (pinfunction "C1_1") (pintype "passive"))
      (node (ref "U$3") (pin "8") (pinfunction "REFIN+_8") (pintype "bidirectional"))
    )
    (net (code "37") (name "Net-(C11-C1)") (class "Default")
      (node (ref "C11") (pin "2") (pinfunction "C1_2") (pintype "passive"))
      (node (ref "U$3") (pin "16") (pinfunction "OSC1_16") (pintype "bidirectional"))
      (node (ref "XTAL2") (pin "3") (pinfunction "3_3") (pintype "passive"))
    )
    (net (code "38") (name "Net-(C12-C1)") (class "Default")
      (node (ref "C12") (pin "2") (pinfunction "C1_2") (pintype "passive"))
      (node (ref "U$3") (pin "17") (pinfunction "OSC2_17") (pintype "bidirectional"))
      (node (ref "XTAL2") (pin "1") (pinfunction "1_1") (pintype "passive"))
    )
    (net (code "39") (name "Net-(C15-C2)") (class "Default")
      (node (ref "C15") (pin "2") (pinfunction "C2_2") (pintype "passive"))
      (node (ref "IC1") (pin "3") (pinfunction "IN+_3") (pintype "input"))
      (node (ref "R19") (pin "2") (pinfunction "R2_2") (pintype "passive"))
      (node (ref "R2") (pin "1") (pinfunction "R1_1") (pintype "passive"))
    )
    (net (code "40") (name "Net-(C22-C1)") (class "Default")
      (node (ref "C22") (pin "2") (pinfunction "C1_2") (pintype "passive"))
      (node (ref "L2") (pin "2") (pinfunction "2_2") (pintype "passive"))
    )
    (net (code "41") (name "Net-(C29-C1)") (class "Default")
      (node (ref "C29") (pin "2") (pinfunction "C1_2") (pintype "passive"))
      (node (ref "U3") (pin "10") (pinfunction "XC1_10") (pintype "input"))
      (node (ref "XTAL3") (pin "3") (pinfunction "3_3") (pintype "passive"))
    )
    (net (code "42") (name "Net-(C30-C1)") (class "Default")
      (node (ref "C30") (pin "2") (pinfunction "C1_2") (pintype "passive"))
      (node (ref "U3") (pin "9") (pinfunction "XC2_9") (pintype "input"))
      (node (ref "XTAL3") (pin "1") (pinfunction "1_1") (pintype "passive"))
    )
    (net (code "43") (name "Net-(C31-C2)") (class "Default")
      (node (ref "C31") (pin "2") (pinfunction "C2_2") (pintype "passive"))
      (node (ref "U3") (pin "19") (pinfunction "DVDD_19") (pintype "power_in"))
    )
    (net (code "44") (name "Net-(C33-C2)") (class "Default")
      (node (ref "C33") (pin "2") (pinfunction "C2_2") (pintype "passive"))
      (node (ref "C34") (pin "1") (pinfunction "C2_1") (pintype "passive"))
      (node (ref "L1") (pin "2") (pinfunction "2_2") (pintype "passive"))
      (node (ref "U3") (pin "11") (pinfunction "VDD_PA_11") (pintype "power_in"))
    )
    (net (code "45") (name "Net-(J1-1)") (class "Default")
      (node (ref "J1") (pin "P$1") (pinfunction "1_P$1") (pintype "passive"))
      (node (ref "R24") (pin "1") (pinfunction "R1_1") (pintype "passive"))
    )
    (net (code "46") (name "Net-(R1-R1)") (class "Default")
      (node (ref "R1") (pin "1") (pinfunction "R1_1") (pintype "passive"))
      (node (ref "U$1") (pin "2") (pinfunction "EN_2") (pintype "bidirectional"))
      (node (ref "U$2") (pin "2") (pinfunction "EN_2") (pintype "bidirectional"))
    )
    (net (code "47") (name "Net-(R9-R2)") (class "Default")
      (node (ref "D5") (pin "-") (pinfunction "-_-") (pintype "passive"))
      (node (ref "R9") (pin "2") (pinfunction "R2_2") (pintype "passive"))
    )
    (net (code "48") (name "Net-(R11-R1)") (class "Default")
      (node (ref "R11") (pin "1") (pinfunction "R1_1") (pintype "passive"))
      (node (ref "U3") (pin "16") (pinfunction "IREF_16") (pintype "input"))
    )
    (net (code "49") (name "Net-(R16-R1)") (class "Default")
      (node (ref "R16") (pin "1") (pinfunction "R1_1") (pintype "passive"))
      (node (ref "U2") (pin "29") (pinfunction "PC6_29") (pintype "bidirectional"))
    )
    (net (code "50") (name "Net-(U2-PB6)") (class "Default")
      (node (ref "D5") (pin "+") (pinfunction "+_+") (pintype "passive"))
      (node (ref "U2") (pin "7") (pinfunction "PB6_7") (pintype "bidirectional"))
    )
    (net (code "51") (name "Net-(U3-ANT1)") (class "Default")
      (node (ref "L1") (pin "1") (pinfunction "1_1") (pintype "passive"))
      (node (ref "L3") (pin "1") (pinfunction "1_1") (pintype "passive"))
      (node (ref "U3") (pin "12") (pinfunction "ANT1_12") (pintype "output"))
    )
    (net (code "52") (name "Net-(U3-ANT2)") (class "Default")
      (node (ref "L2") (pin "1") (pinfunction "1_1") (pintype "passive"))
      (node (ref "L3") (pin "2") (pinfunction "2_2") (pintype "passive"))
      (node (ref "U3") (pin "13") (pinfunction "ANT2_13") (pintype "output"))
    )
    (net (code "53") (name "VCC") (class "Default")
      (node (ref "C2") (pin "2") (pinfunction "C2_2") (pintype "passive"))
      (node (ref "C27") (pin "2") (pinfunction "C2_2") (pintype "passive"))
      (node (ref "C28") (pin "2") (pinfunction "C2_2") (pintype "passive"))
      (node (ref "C32") (pin "1") (pinfunction "C2_1") (pintype "passive"))
      (node (ref "C6") (pin "1") (pinfunction "C1_1") (pintype "passive"))
      (node (ref "C7") (pin "2") (pinfunction "C2_2") (pintype "passive"))
      (node (ref "R13") (pin "2") (pinfunction "R2_2") (pintype "passive"))
      (node (ref "R16") (pin "2") (pinfunction "R2_2") (pintype "passive"))
      (node (ref "R20") (pin "1") (pinfunction "R1_1") (pintype "passive"))
      (node (ref "R21") (pin "1") (pinfunction "R1_1") (pintype "passive"))
      (node (ref "U$1") (pin "4") (pinfunction "OUT_4") (pintype "bidirectional"))
      (node (ref "U$3") (pin "12") (pinfunction "D_VDD_12") (pintype "bidirectional"))
      (node (ref "U$3") (pin "24") (pinfunction "D_VDD_24") (pintype "bidirectional"))
      (node (ref "U1") (pin "12") (pinfunction "VDD_12") (pintype "power_in"))
      (node (ref "U2") (pin "18") (pinfunction "AVCC_18") (pintype "power_in"))
      (node (ref "U2") (pin "4") (pinfunction "VCC_4") (pintype "power_in"))
      (node (ref "U2") (pin "6") (pinfunction "VCC_2_6") (pintype "power_in"))
      (node (ref "U3") (pin "15") (pinfunction "VDD_15") (pintype "power_in"))
      (node (ref "U3") (pin "18") (pinfunction "VDD_18") (pintype "power_in"))
      (node (ref "U3") (pin "7") (pinfunction "VDD_7") (pintype "power_in"))
    )
    (net (code "54") (name "VDD") (class "Default")
      (node (ref "C1") (pin "2") (pinfunction "C2_2") (pintype "passive"))
      (node (ref "C23") (pin "2") (pinfunction "C2_2") (pintype "passive"))
      (node (ref "C8") (pin "2") (pinfunction "C2_2") (pintype "passive"))
      (node (ref "IC1") (pin "8") (pinfunction "VCC+_8") (pintype "power_in"))
      (node (ref "IC2") (pin "2") (pinfunction "VCC+_2") (pintype "power_in"))
      (node (ref "PH4") (pin "1") (pinfunction "1_1") (pintype "bidirectional"))
      (node (ref "R19") (pin "1") (pinfunction "R1_1") (pintype "passive"))
      (node (ref "U$2") (pin "4") (pinfunction "OUT_4") (pintype "bidirectional"))
      (node (ref "U$3") (pin "11") (pinfunction "A_VDD_11") (pintype "bidirectional"))
      (node (ref "U$3") (pin "25") (pinfunction "A_VDD_25") (pintype "bidirectional"))
    )
    (net (code "55") (name "unconnected-(ANTENNA_CHIP1-Pad2)") (class "Default")
      (node (ref "ANTENNA_CHIP1") (pin "2") (pinfunction "2_2") (pintype "passive"))
    )
    (net (code "56") (name "unconnected-(U2-ADC6-Pad19)") (class "Default")
      (node (ref "U2") (pin "19") (pinfunction "ADC6_19") (pintype "input"))
    )
    (net (code "57") (name "unconnected-(U2-ADC7-Pad22)") (class "Default")
      (node (ref "U2") (pin "22") (pinfunction "ADC7_22") (pintype "input"))
    )
    (net (code "58") (name "unconnected-(U2-PB0-Pad12)") (class "Default")
      (node (ref "U2") (pin "12") (pinfunction "PB0_12") (pintype "bidirectional"))
    )
    (net (code "59") (name "unconnected-(U2-PB1-Pad13)") (class "Default")
      (node (ref "U2") (pin "13") (pinfunction "PB1_13") (pintype "bidirectional"))
    )
    (net (code "60") (name "unconnected-(U2-PB2-Pad14)") (class "Default")
      (node (ref "U2") (pin "14") (pinfunction "PB2_14") (pintype "bidirectional"))
    )
    (net (code "61") (name "unconnected-(U2-PB7-Pad8)") (class "Default")
      (node (ref "U2") (pin "8") (pinfunction "PB7_8") (pintype "bidirectional"))
    )
    (net (code "62") (name "unconnected-(U2-PD0-Pad30)") (class "Default")
      (node (ref "U2") (pin "30") (pinfunction "PD0_30") (pintype "bidirectional"))
    )
    (net (code "63") (name "unconnected-(U2-PD1-Pad31)") (class "Default")
      (node (ref "U2") (pin "31") (pinfunction "PD1_31") (pintype "bidirectional"))
    )
    (net (code "64") (name "unconnected-(U2-PD2-Pad32)") (class "Default")
      (node (ref "U2") (pin "32") (pinfunction "PD2_32") (pintype "bidirectional"))
    )
    (net (code "65") (name "unconnected-(U2-PD3-Pad1)") (class "Default")
      (node (ref "U2") (pin "1") (pinfunction "PD3_1") (pintype "bidirectional"))
    )
    (net (code "66") (name "unconnected-(U2-PD4-Pad2)") (class "Default")
      (node (ref "U2") (pin "2") (pinfunction "PD4_2") (pintype "bidirectional"))
    )
    (net (code "67") (name "unconnected-(U2-PD5-Pad9)") (class "Default")
      (node (ref "U2") (pin "9") (pinfunction "PD5_9") (pintype "bidirectional"))
    )
    (net (code "68") (name "unconnected-(U2-PD6-Pad10)") (class "Default")
      (node (ref "U2") (pin "10") (pinfunction "PD6_10") (pintype "bidirectional"))
    )
    (net (code "69") (name "unconnected-(U2-PD7-Pad11)") (class "Default")
      (node (ref "U2") (pin "11") (pinfunction "PD7_11") (pintype "bidirectional"))
    )
    (net (code "70") (name "unconnected-(U3-IRQ-Pad6)") (class "Default")
      (node (ref "U3") (pin "6") (pinfunction "IRQ_6") (pintype "output"))
    )
  )
)
